# PCB_2.net
KiCad netlist of a schematic drawn in EAGLE
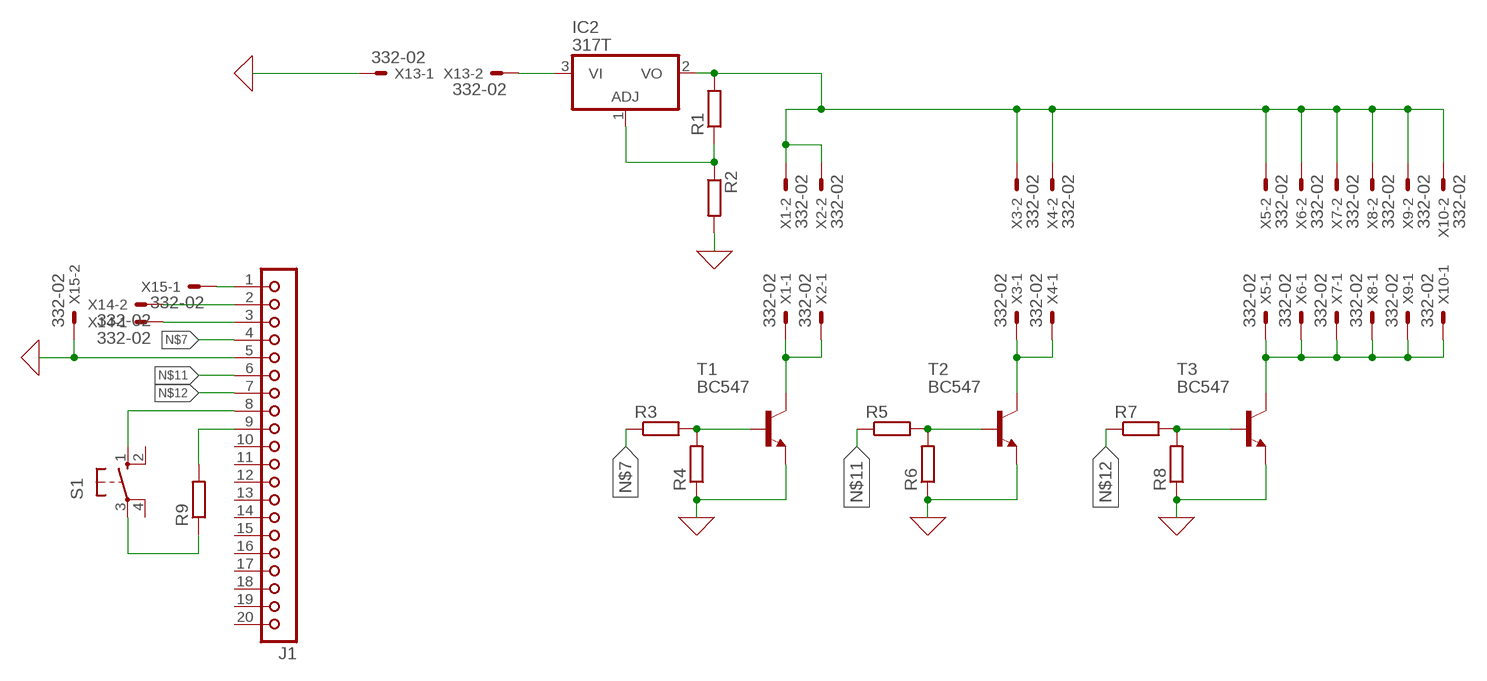
[diagram p0: schematic, sheet 1]

(export (version "E")
  (design (tool "Eeschema 10.0.6"))
  (components
    (comp (ref "IC2")
      (value "317T")
      (footprint "eagle-import:TO220H")
      (libsource (lib "eagle-import") (part "317T"))
    )
    (comp (ref "J1")
      (value "JBK20L")
      (footprint "eagle-import:JBK20L")
      (libsource (lib "eagle-import") (part "JBK20L"))
    )
    (comp (ref "R1")
      (value "R-EU_0309/12")
      (footprint "eagle-import:0309_12")
      (libsource (lib "eagle-import") (part "R-EU_0309/12"))
    )
    (comp (ref "R2")
      (value "R-EU_0309/12")
      (footprint "eagle-import:0309_12")
      (libsource (lib "eagle-import") (part "R-EU_0309/12"))
    )
    (comp (ref "R3")
      (value "R-EU_0309/12")
      (footprint "eagle-import:0309_12")
      (libsource (lib "eagle-import") (part "R-EU_0309/12"))
    )
    (comp (ref "R4")
      (value "R-EU_0309/12")
      (footprint "eagle-import:0309_12")
      (libsource (lib "eagle-import") (part "R-EU_0309/12"))
    )
    (comp (ref "R5")
      (value "R-EU_0309/12")
      (footprint "eagle-import:0309_12")
      (libsource (lib "eagle-import") (part "R-EU_0309/12"))
    )
    (comp (ref "R6")
      (value "R-EU_0309/12")
      (footprint "eagle-import:0309_12")
      (libsource (lib "eagle-import") (part "R-EU_0309/12"))
    )
    (comp (ref "R7")
      (value "R-EU_0309/12")
      (footprint "eagle-import:0309_12")
      (libsource (lib "eagle-import") (part "R-EU_0309/12"))
    )
    (comp (ref "R8")
      (value "R-EU_0309/12")
      (footprint "eagle-import:0309_12")
      (libsource (lib "eagle-import") (part "R-EU_0309/12"))
    )
    (comp (ref "R9")
      (value "R-EU_0309/12")
      (footprint "eagle-import:0309_12")
      (libsource (lib "eagle-import") (part "R-EU_0309/12"))
    )
    (comp (ref "S1")
      (value "10-XX")
      (footprint "eagle-import:B3F-10XX")
      (fields (field (name "MPN") "B3F-1000"))
      (libsource (lib "eagle-import") (part "10-XX"))
    )
    (comp (ref "T1")
      (value "BC547")
      (footprint "eagle-import:TO92")
      (libsource (lib "eagle-import") (part "BC547"))
    )
    (comp (ref "T2")
      (value "BC547")
      (footprint "eagle-import:TO92")
      (libsource (lib "eagle-import") (part "BC547"))
    )
    (comp (ref "T3")
      (value "BC547")
      (footprint "eagle-import:TO92")
      (libsource (lib "eagle-import") (part "BC547"))
    )
    (comp (ref "X1")
      (value "332-02")
      (footprint "eagle-import:332-02")
      (libsource (lib "eagle-import") (part "332-02"))
    )
    (comp (ref "X2")
      (value "332-02")
      (footprint "eagle-import:332-02")
      (libsource (lib "eagle-import") (part "332-02"))
    )
    (comp (ref "X3")
      (value "332-02")
      (footprint "eagle-import:332-02")
      (libsource (lib "eagle-import") (part "332-02"))
    )
    (comp (ref "X4")
      (value "332-02")
      (footprint "eagle-import:332-02")
      (libsource (lib "eagle-import") (part "332-02"))
    )
    (comp (ref "X5")
      (value "332-02")
      (footprint "eagle-import:332-02")
      (libsource (lib "eagle-import") (part "332-02"))
    )
    (comp (ref "X6")
      (value "332-02")
      (footprint "eagle-import:332-02")
      (libsource (lib "eagle-import") (part "332-02"))
    )
    (comp (ref "X7")
      (value "332-02")
      (footprint "eagle-import:332-02")
      (libsource (lib "eagle-import") (part "332-02"))
    )
    (comp (ref "X8")
      (value "332-02")
      (footprint "eagle-import:332-02")
      (libsource (lib "eagle-import") (part "332-02"))
    )
    (comp (ref "X9")
      (value "332-02")
      (footprint "eagle-import:332-02")
      (libsource (lib "eagle-import") (part "332-02"))
    )
    (comp (ref "X10")
      (value "332-02")
      (footprint "eagle-import:332-02")
      (libsource (lib "eagle-import") (part "332-02"))
    )
    (comp (ref "X13")
      (value "332-02")
      (footprint "eagle-import:332-02")
      (libsource (lib "eagle-import") (part "332-02"))
    )
    (comp (ref "X14")
      (value "332-02")
      (footprint "eagle-import:332-02")
      (libsource (lib "eagle-import") (part "332-02"))
    )
    (comp (ref "X15")
      (value "332-02")
      (footprint "eagle-import:332-02")
      (libsource (lib "eagle-import") (part "332-02"))
    )
  )
  (nets
    (net (code "1") (name "GND") (class "Default")
      (node (ref "J1") (pin "5") (pinfunction "5_5") (pintype "passive"))
      (node (ref "R2") (pin "2") (pinfunction "2_2") (pintype "passive"))
      (node (ref "R4") (pin "1") (pinfunction "1_1") (pintype "passive"))
      (node (ref "R6") (pin "1") (pinfunction "1_1") (pintype "passive"))
      (node (ref "R8") (pin "1") (pinfunction "1_1") (pintype "passive"))
      (node (ref "T1") (pin "1") (pinfunction "E_1") (pintype "passive"))
      (node (ref "T2") (pin "1") (pinfunction "E_1") (pintype "passive"))
      (node (ref "T3") (pin "1") (pinfunction "E_1") (pintype "passive"))
      (node (ref "X13") (pin "1") (pinfunction "S_1") (pintype "passive"))
      (node (ref "X15") (pin "2") (pinfunction "S_2") (pintype "passive"))
    )
    (net (code "2") (name "N$7") (class "Default")
      (node (ref "J1") (pin "4") (pinfunction "4_4") (pintype "passive"))
      (node (ref "R3") (pin "1") (pinfunction "1_1") (pintype "passive"))
    )
    (net (code "3") (name "N$11") (class "Default")
      (node (ref "J1") (pin "6") (pinfunction "6_6") (pintype "passive"))
      (node (ref "R5") (pin "1") (pinfunction "1_1") (pintype "passive"))
    )
    (net (code "4") (name "N$12") (class "Default")
      (node (ref "J1") (pin "7") (pinfunction "7_7") (pintype "passive"))
      (node (ref "R7") (pin "1") (pinfunction "1_1") (pintype "passive"))
    )
    (net (code "5") (name "Net-(IC2-ADJ)") (class "Default")
      (node (ref "IC2") (pin "1") (pinfunction "ADJ_1") (pintype "input"))
      (node (ref "R1") (pin "1") (pinfunction "1_1") (pintype "passive"))
      (node (ref "R2") (pin "1") (pinfunction "1_1") (pintype "passive"))
    )
    (net (code "6") (name "Net-(IC2-VI)") (class "Default")
      (node (ref "IC2") (pin "3") (pinfunction "VI_3") (pintype "input"))
      (node (ref "X13") (pin "2") (pinfunction "S_2") (pintype "passive"))
    )
    (net (code "7") (name "Net-(IC2-VO)") (class "Default")
      (node (ref "IC2") (pin "2") (pinfunction "VO_2") (pintype "passive"))
      (node (ref "R1") (pin "2") (pinfunction "2_2") (pintype "passive"))
      (node (ref "X1") (pin "2") (pinfunction "S_2") (pintype "passive"))
      (node (ref "X10") (pin "2") (pinfunction "S_2") (pintype "passive"))
      (node (ref "X2") (pin "2") (pinfunction "S_2") (pintype "passive"))
      (node (ref "X3") (pin "2") (pinfunction "S_2") (pintype "passive"))
      (node (ref "X4") (pin "2") (pinfunction "S_2") (pintype "passive"))
      (node (ref "X5") (pin "2") (pinfunction "S_2") (pintype "passive"))
      (node (ref "X6") (pin "2") (pinfunction "S_2") (pintype "passive"))
      (node (ref "X7") (pin "2") (pinfunction "S_2") (pintype "passive"))
      (node (ref "X8") (pin "2") (pinfunction "S_2") (pintype "passive"))
      (node (ref "X9") (pin "2") (pinfunction "S_2") (pintype "passive"))
    )
    (net (code "8") (name "Net-(J1-Pad9)") (class "Default")
      (node (ref "J1") (pin "9") (pinfunction "9_9") (pintype "passive"))
      (node (ref "R9") (pin "2") (pinfunction "2_2") (pintype "passive"))
    )
    (net (code "9") (name "Net-(S1-P)") (class "Default")
      (node (ref "R9") (pin "1") (pinfunction "1_1") (pintype "passive"))
      (node (ref "S1") (pin "3") (pinfunction "P_3") (pintype "passive"))
    )
    (net (code "10") (name "Net-(S1-S)") (class "Default")
      (node (ref "J1") (pin "8") (pinfunction "8_8") (pintype "passive"))
      (node (ref "S1") (pin "1") (pinfunction "S_1") (pintype "passive"))
    )
    (net (code "11") (name "Net-(T1-B)") (class "Default")
      (node (ref "R3") (pin "2") (pinfunction "2_2") (pintype "passive"))
      (node (ref "R4") (pin "2") (pinfunction "2_2") (pintype "passive"))
      (node (ref "T1") (pin "2") (pinfunction "B_2") (pintype "passive"))
    )
    (net (code "12") (name "Net-(T1-C)") (class "Default")
      (node (ref "T1") (pin "3") (pinfunction "C_3") (pintype "passive"))
      (node (ref "X1") (pin "1") (pinfunction "S_1") (pintype "passive"))
      (node (ref "X2") (pin "1") (pinfunction "S_1") (pintype "passive"))
    )
    (net (code "13") (name "Net-(T2-B)") (class "Default")
      (node (ref "R5") (pin "2") (pinfunction "2_2") (pintype "passive"))
      (node (ref "R6") (pin "2") (pinfunction "2_2") (pintype "passive"))
      (node (ref "T2") (pin "2") (pinfunction "B_2") (pintype "passive"))
    )
    (net (code "14") (name "Net-(T2-C)") (class "Default")
      (node (ref "T2") (pin "3") (pinfunction "C_3") (pintype "passive"))
      (node (ref "X3") (pin "1") (pinfunction "S_1") (pintype "passive"))
      (node (ref "X4") (pin "1") (pinfunction "S_1") (pintype "passive"))
    )
    (net (code "15") (name "Net-(T3-B)") (class "Default")
      (node (ref "R7") (pin "2") (pinfunction "2_2") (pintype "passive"))
      (node (ref "R8") (pin "2") (pinfunction "2_2") (pintype "passive"))
      (node (ref "T3") (pin "2") (pinfunction "B_2") (pintype "passive"))
    )
    (net (code "16") (name "Net-(T3-C)") (class "Default")
      (node (ref "T3") (pin "3") (pinfunction "C_3") (pintype "passive"))
      (node (ref "X10") (pin "1") (pinfunction "S_1") (pintype "passive"))
      (node (ref "X5") (pin "1") (pinfunction "S_1") (pintype "passive"))
      (node (ref "X6") (pin "1") (pinfunction "S_1") (pintype "passive"))
      (node (ref "X7") (pin "1") (pinfunction "S_1") (pintype "passive"))
      (node (ref "X8") (pin "1") (pinfunction "S_1") (pintype "passive"))
      (node (ref "X9") (pin "1") (pinfunction "S_1") (pintype "passive"))
    )
    (net (code "17") (name "Net-(X14A-S)") (class "Default")
      (node (ref "J1") (pin "3") (pinfunction "3_3") (pintype "passive"))
      (node (ref "X14") (pin "1") (pinfunction "S_1") (pintype "passive"))
    )
    (net (code "18") (name "Net-(X14B-S)") (class "Default")
      (node (ref "J1") (pin "2") (pinfunction "2_2") (pintype "passive"))
      (node (ref "X14") (pin "2") (pinfunction "S_2") (pintype "passive"))
    )
    (net (code "19") (name "Net-(X15A-S)") (class "Default")
      (node (ref "J1") (pin "1") (pinfunction "1_1") (pintype "passive"))
      (node (ref "X15") (pin "1") (pinfunction "S_1") (pintype "passive"))
    )
    (net (code "20") (name "unconnected-(J1-Pad10)") (class "Default")
      (node (ref "J1") (pin "10") (pinfunction "10_10") (pintype "passive"))
    )
    (net (code "21") (name "unconnected-(J1-Pad11)") (class "Default")
      (node (ref "J1") (pin "11") (pinfunction "11_11") (pintype "passive"))
    )
    (net (code "22") (name "unconnected-(J1-Pad12)") (class "Default")
      (node (ref "J1") (pin "12") (pinfunction "12_12") (pintype "passive"))
    )
    (net (code "23") (name "unconnected-(J1-Pad13)") (class "Default")
      (node (ref "J1") (pin "13") (pinfunction "13_13") (pintype "passive"))
    )
    (net (code "24") (name "unconnected-(J1-Pad14)") (class "Default")
      (node (ref "J1") (pin "14") (pinfunction "14_14") (pintype "passive"))
    )
    (net (code "25") (name "unconnected-(J1-Pad15)") (class "Default")
      (node (ref "J1") (pin "15") (pinfunction "15_15") (pintype "passive"))
    )
    (net (code "26") (name "unconnected-(J1-Pad16)") (class "Default")
      (node (ref "J1") (pin "16") (pinfunction "16_16") (pintype "passive"))
    )
    (net (code "27") (name "unconnected-(J1-Pad17)") (class "Default")
      (node (ref "J1") (pin "17") (pinfunction "17_17") (pintype "passive"))
    )
    (net (code "28") (name "unconnected-(J1-Pad18)") (class "Default")
      (node (ref "J1") (pin "18") (pinfunction "18_18") (pintype "passive"))
    )
    (net (code "29") (name "unconnected-(J1-Pad19)") (class "Default")
      (node (ref "J1") (pin "19") (pinfunction "19_19") (pintype "passive"))
    )
    (net (code "30") (name "unconnected-(J1-Pad20)") (class "Default")
      (node (ref "J1") (pin "20") (pinfunction "20_20") (pintype "passive"))
    )
    (net (code "31") (name "unconnected-(S1-P1-Pad4)") (class "Default")
      (node (ref "S1") (pin "4") (pinfunction "P1_4") (pintype "passive"))
    )
    (net (code "32") (name "unconnected-(S1-S1-Pad2)") (class "Default")
      (node (ref "S1") (pin "2") (pinfunction "S1_2") (pintype "passive"))
    )
  )
)
